# TempRFOut.net
KiCad netlist of a schematic drawn in Altium Designer
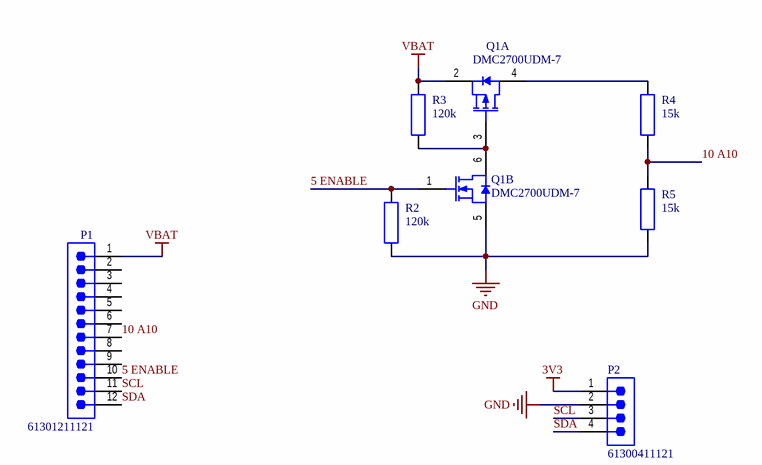
[diagram p0: TempRFOut.SchDoc]

(export (version "E")
  (design (tool "Eeschema 10.0.6"))
  (components
    (comp (ref "P1")
      (value "61301211121")
      (footprint "61301211121")
      (description "THT Vertical Pin Header WR-PHD, Pitch 2.54 mm, Single Row, 12 pins")
      (libsource (lib "Altium Content Vault") (part "Header_Male_1R_12P"))
    )
    (comp (ref "P2")
      (value "61300411121")
      (footprint "61300411121")
      (description "THT Vertical Pin Header WR-PHD, Pitch 2.54 mm, Single Row, 4 pins")
      (libsource (lib "Altium Content Vault") (part "Header_Male_1R_04P"))
    )
    (comp (ref "Q1")
      (value "DMC2700UDM-7")
      (footprint "FAIR-SOT23-6_V")
      (fields (field (name "MANUFACTURER") "Fairchild"))
      (libsource (lib "Altium Content Vault") (part "PEMOS-SGD-NEMOS-GSD-6"))
    )
    (comp (ref "R2")
      (value "120k")
      (footprint "0603")
      (description "Resistor")
      (libsource (lib "MyProtel_1") (part "R"))
    )
    (comp (ref "R3")
      (value "120k")
      (footprint "0603")
      (description "Resistor")
      (libsource (lib "MyProtel_1") (part "R"))
    )
    (comp (ref "R4")
      (value "15k")
      (footprint "0603")
      (description "Resistor")
      (libsource (lib "MyProtel_1") (part "R"))
    )
    (comp (ref "R5")
      (value "15k")
      (footprint "0603")
      (description "Resistor")
      (libsource (lib "MyProtel_1") (part "R"))
    )
  )
  (nets
    (net (code "1") (name "/5 ENABLE") (class "Default")
      (node (ref "P1") (pin "10") (pinfunction "10_10") (pintype "passive"))
      (node (ref "Q1") (pin "1") (pinfunction "G_1") (pintype "passive"))
      (node (ref "R2") (pin "2") (pintype "passive"))
    )
    (net (code "2") (name "/10 A10") (class "Default")
      (node (ref "P1") (pin "7") (pinfunction "7_7") (pintype "passive"))
      (node (ref "R4") (pin "1") (pintype "passive"))
      (node (ref "R5") (pin "2") (pintype "passive"))
    )
    (net (code "3") (name "/SCL") (class "Default")
      (node (ref "P1") (pin "11") (pinfunction "11_11") (pintype "passive"))
      (node (ref "P2") (pin "3") (pinfunction "3_3") (pintype "passive"))
    )
    (net (code "4") (name "/SDA") (class "Default")
      (node (ref "P1") (pin "12") (pinfunction "12_12") (pintype "passive"))
      (node (ref "P2") (pin "4") (pinfunction "4_4") (pintype "passive"))
    )
    (net (code "5") (name "3V3") (class "Default")
      (node (ref "P2") (pin "1") (pinfunction "1_1") (pintype "passive"))
    )
    (net (code "6") (name "GND") (class "Default")
      (node (ref "P2") (pin "2") (pinfunction "2_2") (pintype "passive"))
      (node (ref "Q1") (pin "5") (pinfunction "S_5") (pintype "passive"))
      (node (ref "R2") (pin "1") (pintype "passive"))
      (node (ref "R5") (pin "1") (pintype "passive"))
    )
    (net (code "7") (name "Net-(Q1A-D)") (class "Default")
      (node (ref "Q1") (pin "4") (pinfunction "D_4") (pintype "passive"))
      (node (ref "R4") (pin "2") (pintype "passive"))
    )
    (net (code "8") (name "Net-(Q1A-G)") (class "Default")
      (node (ref "Q1") (pin "3") (pinfunction "G_3") (pintype "passive"))
      (node (ref "Q1") (pin "6") (pinfunction "D_6") (pintype "passive"))
      (node (ref "R3") (pin "1") (pintype "passive"))
    )
    (net (code "9") (name "VBAT") (class "Default")
      (node (ref "P1") (pin "1") (pinfunction "1_1") (pintype "passive"))
      (node (ref "Q1") (pin "2") (pinfunction "S_2") (pintype "passive"))
      (node (ref "R3") (pin "2") (pintype "passive"))
    )
    (net (code "10") (name "unconnected-(P1-Pad2)") (class "Default")
      (node (ref "P1") (pin "2") (pinfunction "2_2") (pintype "passive"))
    )
    (net (code "11") (name "unconnected-(P1-Pad3)") (class "Default")
      (node (ref "P1") (pin "3") (pinfunction "3_3") (pintype "passive"))
    )
    (net (code "12") (name "unconnected-(P1-Pad4)") (class "Default")
      (node (ref "P1") (pin "4") (pinfunction "4_4") (pintype "passive"))
    )
    (net (code "13") (name "unconnected-(P1-Pad5)") (class "Default")
      (node (ref "P1") (pin "5") (pinfunction "5_5") (pintype "passive"))
    )
    (net (code "14") (name "unconnected-(P1-Pad6)") (class "Default")
      (node (ref "P1") (pin "6") (pinfunction "6_6") (pintype "passive"))
    )
    (net (code "15") (name "unconnected-(P1-Pad8)") (class "Default")
      (node (ref "P1") (pin "8") (pinfunction "8_8") (pintype "passive"))
    )
    (net (code "16") (name "unconnected-(P1-Pad9)") (class "Default")
      (node (ref "P1") (pin "9") (pinfunction "9_9") (pintype "passive"))
    )
  )
)
